# SX1308.net
KiCad netlist of a schematic drawn in Altium Designer
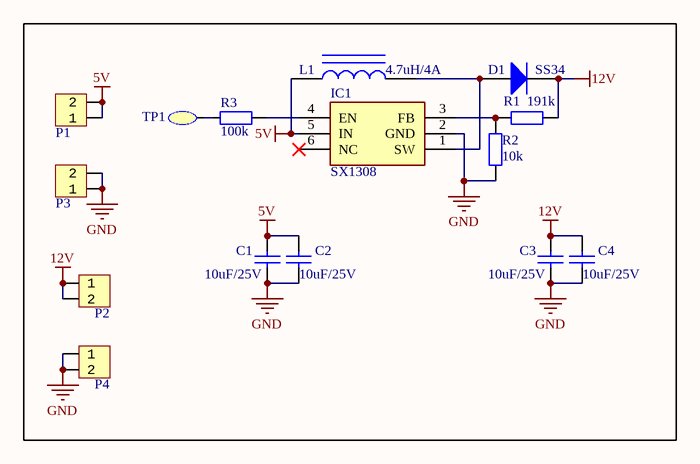
[diagram p0: SX1308.SchDoc]

(export (version "E")
  (design (tool "Eeschema 10.0.6"))
  (components
    (comp (ref "C1")
      (value "10uF/25V")
      (footprint "CAP-0603")
      (description "X7R")
      (libsource (lib "Power_Lib_Altium") (part "CAP"))
    )
    (comp (ref "C2")
      (value "10uF/25V")
      (footprint "CAP-0603")
      (description "X7R")
      (libsource (lib "Power_Lib_Altium") (part "CAP"))
    )
    (comp (ref "C3")
      (value "10uF/25V")
      (footprint "CAP-0603")
      (description "X7R")
      (libsource (lib "Power_Lib_Altium") (part "CAP"))
    )
    (comp (ref "C4")
      (value "10uF/25V")
      (footprint "CAP-0603")
      (description "X7R")
      (libsource (lib "Power_Lib_Altium") (part "CAP"))
    )
    (comp (ref "D1")
      (value "SS34")
      (footprint "DO-214AC_SMA")
      (description "肖特基二极管")
      (libsource (lib "Power_Lib_Altium") (part "DIODE"))
    )
    (comp (ref "IC1")
      (value "SX1308")
      (footprint "SOT-23-6")
      (description "集成升压芯片")
      (libsource (lib "Power_Lib_Altium") (part "SX1308"))
    )
    (comp (ref "L1")
      (value "4.7uH/4A")
      (footprint "SMD_7.3x7.3x4.2mm")
      (description "电感")
      (libsource (lib "Power_Lib_Altium") (part "INDUCTOR"))
    )
    (comp (ref "P1")
      (value "HDR1x2_2.54")
      (footprint "HDR1X2_2.54_180")
      (description "Header")
      (libsource (lib "Power_Lib_Altium") (part "HDR1x2_2.54"))
    )
    (comp (ref "P2")
      (value "HDR1x2_2.54")
      (footprint "HDR1X2_2.54_180")
      (description "Header")
      (libsource (lib "") (part "HDR1x2_2.54_1"))
    )
    (comp (ref "P3")
      (value "HDR1x2_2.54")
      (footprint "HDR1X2_2.54_180")
      (description "Header")
      (libsource (lib "Power_Lib_Altium") (part "HDR1x2_2.54"))
    )
    (comp (ref "P4")
      (value "HDR1x2_2.54")
      (footprint "HDR1X2_2.54_180")
      (description "Header")
      (libsource (lib "") (part "HDR1x2_2.54_1"))
    )
    (comp (ref "R1")
      (value "191k")
      (footprint "R-0603")
      (description "贴片电阻")
      (libsource (lib "") (part "RES_1"))
    )
    (comp (ref "R2")
      (value "10k")
      (footprint "R-0603")
      (description "贴片电阻")
      (libsource (lib "Power_Lib_Altium") (part "RES"))
    )
    (comp (ref "R3")
      (value "100k")
      (footprint "R-0603")
      (description "贴片电阻")
      (libsource (lib "") (part "RES_1"))
    )
    (comp (ref "TP1")
      (value "TestPoint")
      (footprint "TestPoint")
      (description "测试点")
      (libsource (lib "Power_Lib_Altium") (part "TestPoint"))
    )
  )
  (nets
    (net (code "1") (name "5V") (class "Default")
      (node (ref "C1") (pin "2") (pinfunction "2_2") (pintype "passive"))
      (node (ref "C2") (pin "2") (pinfunction "2_2") (pintype "passive"))
      (node (ref "IC1") (pin "5") (pinfunction "IN_5") (pintype "passive"))
      (node (ref "L1") (pin "1") (pinfunction "1_1") (pintype "passive"))
      (node (ref "P1") (pin "1") (pinfunction "1_1") (pintype "passive"))
      (node (ref "P1") (pin "2") (pinfunction "2_2") (pintype "passive"))
    )
    (net (code "2") (name "12V") (class "Default")
      (node (ref "C3") (pin "2") (pinfunction "2_2") (pintype "passive"))
      (node (ref "C4") (pin "2") (pinfunction "2_2") (pintype "passive"))
      (node (ref "D1") (pin "2") (pinfunction "K_2") (pintype "passive"))
      (node (ref "P2") (pin "1") (pinfunction "1_1") (pintype "passive"))
      (node (ref "P2") (pin "2") (pinfunction "2_2") (pintype "passive"))
      (node (ref "R1") (pin "2") (pinfunction "2_2") (pintype "passive"))
    )
    (net (code "3") (name "GND") (class "Default")
      (node (ref "C1") (pin "1") (pinfunction "1_1") (pintype "passive"))
      (node (ref "C2") (pin "1") (pinfunction "1_1") (pintype "passive"))
      (node (ref "C3") (pin "1") (pinfunction "1_1") (pintype "passive"))
      (node (ref "C4") (pin "1") (pinfunction "1_1") (pintype "passive"))
      (node (ref "IC1") (pin "2") (pinfunction "GND_2") (pintype "passive"))
      (node (ref "P3") (pin "1") (pinfunction "1_1") (pintype "passive"))
      (node (ref "P3") (pin "2") (pinfunction "2_2") (pintype "passive"))
      (node (ref "P4") (pin "1") (pinfunction "1_1") (pintype "passive"))
      (node (ref "P4") (pin "2") (pinfunction "2_2") (pintype "passive"))
      (node (ref "R2") (pin "1") (pinfunction "1_1") (pintype "passive"))
    )
    (net (code "4") (name "Net-(D1-A)") (class "Default")
      (node (ref "D1") (pin "1") (pinfunction "A_1") (pintype "passive"))
      (node (ref "IC1") (pin "1") (pinfunction "SW_1") (pintype "passive"))
      (node (ref "L1") (pin "2") (pinfunction "2_2") (pintype "passive"))
    )
    (net (code "5") (name "Net-(IC1-EN)") (class "Default")
      (node (ref "IC1") (pin "4") (pinfunction "EN_4") (pintype "passive"))
      (node (ref "R3") (pin "2") (pinfunction "2_2") (pintype "passive"))
    )
    (net (code "6") (name "Net-(IC1-FB)") (class "Default")
      (node (ref "IC1") (pin "3") (pinfunction "FB_3") (pintype "passive"))
      (node (ref "R1") (pin "1") (pinfunction "1_1") (pintype "passive"))
      (node (ref "R2") (pin "2") (pinfunction "2_2") (pintype "passive"))
    )
    (net (code "7") (name "Net-(R3-Pad1)") (class "Default")
      (node (ref "R3") (pin "1") (pinfunction "1_1") (pintype "passive"))
      (node (ref "TP1") (pin "1") (pinfunction "1_1") (pintype "passive"))
    )
    (net (code "8") (name "unconnected-(IC1-NC-Pad6)") (class "Default")
      (node (ref "IC1") (pin "6") (pinfunction "NC_6") (pintype "passive+no_connect"))
    )
  )
)
